# ioniq-v2.net
KiCad netlist of a schematic drawn in EAGLE
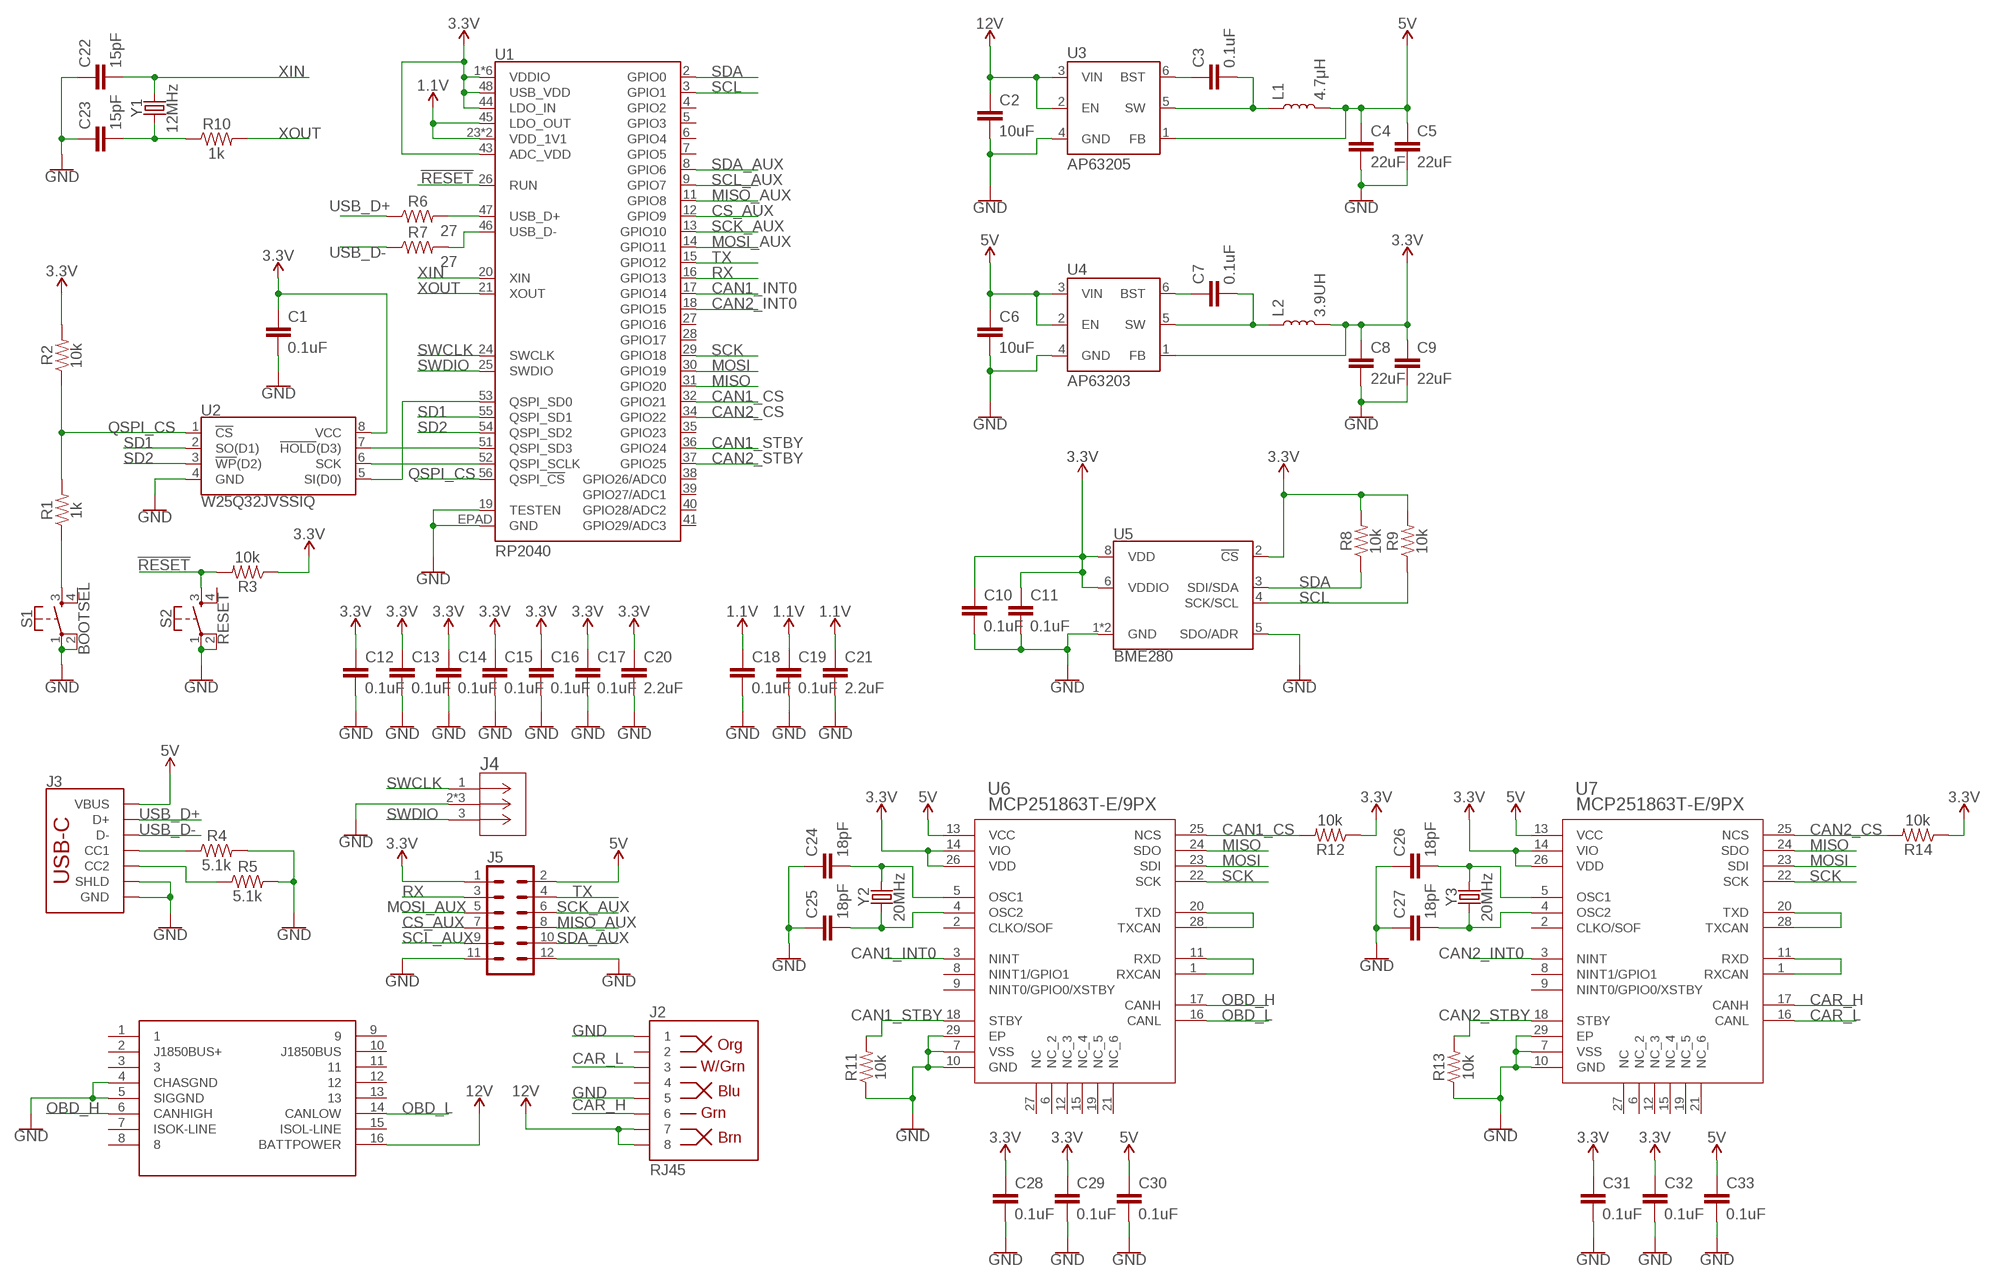
[diagram p0: schematic, sheet 1]

(export (version "E")
  (design (tool "Eeschema 10.0.6"))
  (components
    (comp (ref "C1")
      (value "0.1uF")
      (footprint "eagle-import:0603")
      (libsource (lib "eagle-import") (part "0.1UF-0603-25V-10%-X7R-WE"))
    )
    (comp (ref "C2")
      (value "10uF")
      (footprint "eagle-import:0805")
      (libsource (lib "eagle-import") (part "10UF-0805-25V-10%"))
    )
    (comp (ref "C3")
      (value "0.1uF")
      (footprint "eagle-import:0603")
      (libsource (lib "eagle-import") (part "0.1UF-0603-25V-5%"))
    )
    (comp (ref "C4")
      (value "22uF")
      (footprint "eagle-import:0603")
      (libsource (lib "eagle-import") (part "22UF-0603-6.3V-20%"))
    )
    (comp (ref "C5")
      (value "22uF")
      (footprint "eagle-import:0603")
      (libsource (lib "eagle-import") (part "22UF-0603-6.3V-20%"))
    )
    (comp (ref "C6")
      (value "10uF")
      (footprint "eagle-import:0805")
      (libsource (lib "eagle-import") (part "10UF-0805-25V-10%"))
    )
    (comp (ref "C7")
      (value "0.1uF")
      (footprint "eagle-import:0603")
      (libsource (lib "eagle-import") (part "0.1UF-0603-25V-5%"))
    )
    (comp (ref "C8")
      (value "22uF")
      (footprint "eagle-import:0603")
      (libsource (lib "eagle-import") (part "22UF-0603-6.3V-20%"))
    )
    (comp (ref "C9")
      (value "22uF")
      (footprint "eagle-import:0603")
      (libsource (lib "eagle-import") (part "22UF-0603-6.3V-20%"))
    )
    (comp (ref "C10")
      (value "0.1uF")
      (footprint "eagle-import:0603")
      (libsource (lib "eagle-import") (part "0.1UF-0603-25V-10%-X7R-WE"))
    )
    (comp (ref "C11")
      (value "0.1uF")
      (footprint "eagle-import:0603")
      (libsource (lib "eagle-import") (part "0.1UF-0603-25V-10%-X7R-WE"))
    )
    (comp (ref "C12")
      (value "0.1uF")
      (footprint "eagle-import:0603")
      (libsource (lib "eagle-import") (part "0.1UF-0603-25V-10%-X7R-WE"))
    )
    (comp (ref "C13")
      (value "0.1uF")
      (footprint "eagle-import:0603")
      (libsource (lib "eagle-import") (part "0.1UF-0603-25V-10%-X7R-WE"))
    )
    (comp (ref "C14")
      (value "0.1uF")
      (footprint "eagle-import:0603")
      (libsource (lib "eagle-import") (part "0.1UF-0603-25V-10%-X7R-WE"))
    )
    (comp (ref "C15")
      (value "0.1uF")
      (footprint "eagle-import:0603")
      (libsource (lib "eagle-import") (part "0.1UF-0603-25V-10%-X7R-WE"))
    )
    (comp (ref "C16")
      (value "0.1uF")
      (footprint "eagle-import:0603")
      (libsource (lib "eagle-import") (part "0.1UF-0603-25V-10%-X7R-WE"))
    )
    (comp (ref "C17")
      (value "0.1uF")
      (footprint "eagle-import:0603")
      (libsource (lib "eagle-import") (part "0.1UF-0603-25V-10%-X7R-WE"))
    )
    (comp (ref "C18")
      (value "0.1uF")
      (footprint "eagle-import:0603")
      (libsource (lib "eagle-import") (part "0.1UF-0603-25V-10%-X7R-WE"))
    )
    (comp (ref "C19")
      (value "0.1uF")
      (footprint "eagle-import:0603")
      (libsource (lib "eagle-import") (part "0.1UF-0603-25V-10%-X7R-WE"))
    )
    (comp (ref "C20")
      (value "2.2uF")
      (footprint "eagle-import:0603")
      (libsource (lib "eagle-import") (part "2.2UF-0603-10V-20%"))
    )
    (comp (ref "C21")
      (value "2.2uF")
      (footprint "eagle-import:0603")
      (libsource (lib "eagle-import") (part "2.2UF-0603-10V-20%"))
    )
    (comp (ref "C22")
      (value "15pF")
      (footprint "eagle-import:0603")
      (libsource (lib "eagle-import") (part "15PF-0603-50V-5%"))
    )
    (comp (ref "C23")
      (value "15pF")
      (footprint "eagle-import:0603")
      (libsource (lib "eagle-import") (part "15PF-0603-50V-5%"))
    )
    (comp (ref "C24")
      (value "18pF")
      (footprint "eagle-import:0603")
      (libsource (lib "eagle-import") (part "18PF-0603-50V-5%"))
    )
    (comp (ref "C25")
      (value "18pF")
      (footprint "eagle-import:0603")
      (libsource (lib "eagle-import") (part "18PF-0603-50V-5%"))
    )
    (comp (ref "C26")
      (value "18pF")
      (footprint "eagle-import:0603")
      (libsource (lib "eagle-import") (part "18PF-0603-50V-5%"))
    )
    (comp (ref "C27")
      (value "18pF")
      (footprint "eagle-import:0603")
      (libsource (lib "eagle-import") (part "18PF-0603-50V-5%"))
    )
    (comp (ref "C28")
      (value "0.1uF")
      (footprint "eagle-import:0603")
      (libsource (lib "eagle-import") (part "0.1UF-0603-25V-10%-X7R-WE"))
    )
    (comp (ref "C29")
      (value "0.1uF")
      (footprint "eagle-import:0603")
      (libsource (lib "eagle-import") (part "0.1UF-0603-25V-10%-X7R-WE"))
    )
    (comp (ref "C30")
      (value "0.1uF")
      (footprint "eagle-import:0603")
      (libsource (lib "eagle-import") (part "0.1UF-0603-25V-10%-X7R-WE"))
    )
    (comp (ref "C31")
      (value "0.1uF")
      (footprint "eagle-import:0603")
      (libsource (lib "eagle-import") (part "0.1UF-0603-25V-10%-X7R-WE"))
    )
    (comp (ref "C32")
      (value "0.1uF")
      (footprint "eagle-import:0603")
      (libsource (lib "eagle-import") (part "0.1UF-0603-25V-10%-X7R-WE"))
    )
    (comp (ref "C33")
      (value "0.1uF")
      (footprint "eagle-import:0603")
      (libsource (lib "eagle-import") (part "0.1UF-0603-25V-10%-X7R-WE"))
    )
    (comp (ref "J1")
      (value "OBDII")
      (footprint "eagle-import:OBDII")
      (libsource (lib "eagle-import") (part "OBDII"))
    )
    (comp (ref "J2")
      (value "RJ45")
      (footprint "eagle-import:RJ45-8")
      (libsource (lib "eagle-import") (part "RJ45-8"))
    )
    (comp (ref "J3")
      (value "USB_C_2-LAYER_PADS")
      (footprint "eagle-import:USB-C-16P-2LAYER-PADS")
      (libsource (lib "eagle-import") (part "USB_C_2-LAYER_PADS"))
    )
    (comp (ref "J4")
      (value "BM03B-SRSS-TB(LF)(SN)")
      (footprint "eagle-import:CONN_BM03B-SRSS-TB(LF)(SN)_JST")
      (fields (field (name "COPYRIGHT") "Copyright (C) 2024 Ultra Librarian. All rights reserved."))
      (libsource (lib "eagle-import") (part "BM03B-SRSS-TB(LF)(SN)"))
    )
    (comp (ref "J5")
      (value "2X6 FEMALE")
      (footprint "eagle-import:2X6")
      (libsource (lib "eagle-import") (part "CONN_06X2PTH_FEMALE"))
    )
    (comp (ref "L1")
      (value "4.7μH")
      (footprint "eagle-import:INDUCTOR_4X4MM")
      (libsource (lib "eagle-import") (part "4.7μH_SHIELDED_INDUCTORNPIS_LS"))
    )
    (comp (ref "L2")
      (value "3.9UH")
      (footprint "eagle-import:INDUCTOR_3.9UH")
      (libsource (lib "eagle-import") (part "3.9UH"))
    )
    (comp (ref "R1")
      (value "1k")
      (footprint "eagle-import:0603")
      (libsource (lib "eagle-import") (part "1KOHM-0603-1/10W-1%"))
    )
    (comp (ref "R2")
      (value "10k")
      (footprint "eagle-import:0603")
      (libsource (lib "eagle-import") (part "10KOHM-0603-1/10W-1%"))
    )
    (comp (ref "R3")
      (value "10k")
      (footprint "eagle-import:0603")
      (libsource (lib "eagle-import") (part "10KOHM-0603-1/10W-1%"))
    )
    (comp (ref "R4")
      (value "5.1k")
      (footprint "eagle-import:0603")
      (libsource (lib "eagle-import") (part "5.1KOHM5.1KOHM-0603-1/10W-1%"))
    )
    (comp (ref "R5")
      (value "5.1k")
      (footprint "eagle-import:0603")
      (libsource (lib "eagle-import") (part "5.1KOHM5.1KOHM-0603-1/10W-1%"))
    )
    (comp (ref "R6")
      (value "27")
      (footprint "eagle-import:0603")
      (libsource (lib "eagle-import") (part "27OHM-0603-1/10W-1%"))
    )
    (comp (ref "R7")
      (value "27")
      (footprint "eagle-import:0603")
      (libsource (lib "eagle-import") (part "27OHM-0603-1/10W-1%"))
    )
    (comp (ref "R8")
      (value "10k")
      (footprint "eagle-import:0603")
      (libsource (lib "eagle-import") (part "10KOHM-0603-1/10W-1%"))
    )
    (comp (ref "R9")
      (value "10k")
      (footprint "eagle-import:0603")
      (libsource (lib "eagle-import") (part "10KOHM-0603-1/10W-1%"))
    )
    (comp (ref "R10")
      (value "1k")
      (footprint "eagle-import:0603")
      (libsource (lib "eagle-import") (part "1KOHM-0603-1/10W-1%"))
    )
    (comp (ref "R11")
      (value "10k")
      (footprint "eagle-import:0603")
      (libsource (lib "eagle-import") (part "10KOHM-0603-1/10W-1%"))
    )
    (comp (ref "R12")
      (value "10k")
      (footprint "eagle-import:0603")
      (libsource (lib "eagle-import") (part "10KOHM-0603-1/10W-1%"))
    )
    (comp (ref "R13")
      (value "10k")
      (footprint "eagle-import:0603")
      (libsource (lib "eagle-import") (part "10KOHM-0603-1/10W-1%"))
    )
    (comp (ref "R14")
      (value "10k")
      (footprint "eagle-import:0603")
      (libsource (lib "eagle-import") (part "10KOHM-0603-1/10W-1%"))
    )
    (comp (ref "S1")
      (value "BOOTSEL")
      (footprint "eagle-import:TACTILE_SWITCH_SMD_4.6X2.8MM")
      (libsource (lib "eagle-import") (part "MOMENTARY-SWITCH-SPST-2-SMD-4.6X2.8MM"))
    )
    (comp (ref "S2")
      (value "RESET")
      (footprint "eagle-import:TACTILE_SWITCH_SMD_4.6X2.8MM")
      (libsource (lib "eagle-import") (part "MOMENTARY-SWITCH-SPST-2-SMD-4.6X2.8MM"))
    )
    (comp (ref "U1")
      (value "RP2040")
      (footprint "eagle-import:QFN-56")
      (libsource (lib "eagle-import") (part "RP2040"))
    )
    (comp (ref "U2")
      (value "W25Q32JVSSIQ")
      (footprint "eagle-import:SOIC-8")
      (libsource (lib "eagle-import") (part "W25Q32FVSS"))
    )
    (comp (ref "U3")
      (value "AP63205")
      (footprint "eagle-import:SOT23-6")
      (libsource (lib "eagle-import") (part "AP63203"))
    )
    (comp (ref "U4")
      (value "AP63203")
      (footprint "eagle-import:SOT23-6")
      (libsource (lib "eagle-import") (part "AP63203"))
    )
    (comp (ref "U5")
      (value "BME280")
      (footprint "eagle-import:LGA-8-2.5X2.5")
      (libsource (lib "eagle-import") (part "BME280"))
    )
    (comp (ref "U6")
      (value "MCP251863T-E/9PX")
      (footprint "eagle-import:VQFN28_9PX_3P25X3P25EPAD_MCH")
      (fields (field (name "COPYRIGHT") "Copyright (C) 2024 Ultra Librarian. All rights reserved."))
      (libsource (lib "eagle-import") (part "MCP251863T-E/9PX"))
    )
    (comp (ref "U7")
      (value "MCP251863T-E/9PX")
      (footprint "eagle-import:VQFN28_9PX_3P25X3P25EPAD_MCH")
      (fields (field (name "COPYRIGHT") "Copyright (C) 2024 Ultra Librarian. All rights reserved."))
      (libsource (lib "eagle-import") (part "MCP251863T-E/9PX"))
    )
    (comp (ref "Y1")
      (value "12MHz")
      (footprint "eagle-import:CRYSTAL-SMD-3.2X2.5MM")
      (libsource (lib "eagle-import") (part "CRYSTALSMD-3.2X2.5"))
    )
    (comp (ref "Y2")
      (value "20MHz")
      (footprint "eagle-import:CRYSTAL-SMD-3.2X2.5MM")
      (libsource (lib "eagle-import") (part "CRYSTALSMD-3.2X2.5"))
    )
    (comp (ref "Y3")
      (value "20MHz")
      (footprint "eagle-import:CRYSTAL-SMD-3.2X2.5MM")
      (libsource (lib "eagle-import") (part "CRYSTALSMD-3.2X2.5"))
    )
  )
  (nets
    (net (code "1") (name "/CAN1_CS") (class "Default")
      (node (ref "R12") (pin "2") (pinfunction "2_2") (pintype "passive"))
      (node (ref "U1") (pin "32") (pinfunction "GPIO21_32") (pintype "bidirectional"))
      (node (ref "U6") (pin "25") (pinfunction "NCS_25") (pintype "input"))
    )
    (net (code "2") (name "/CAN1_INT0") (class "Default")
      (node (ref "U1") (pin "17") (pinfunction "GPIO14_17") (pintype "bidirectional"))
      (node (ref "U6") (pin "3") (pinfunction "NINT_3") (pintype "output"))
    )
    (net (code "3") (name "/CAN1_STBY") (class "Default")
      (node (ref "R11") (pin "2") (pinfunction "2_2") (pintype "passive"))
      (node (ref "U1") (pin "36") (pinfunction "GPIO24_36") (pintype "bidirectional"))
      (node (ref "U6") (pin "18") (pinfunction "STBY_18") (pintype "input"))
    )
    (net (code "4") (name "/CAN2_CS") (class "Default")
      (node (ref "R14") (pin "2") (pinfunction "2_2") (pintype "passive"))
      (node (ref "U1") (pin "34") (pinfunction "GPIO22_34") (pintype "bidirectional"))
      (node (ref "U7") (pin "25") (pinfunction "NCS_25") (pintype "input"))
    )
    (net (code "5") (name "/CAN2_INT0") (class "Default")
      (node (ref "U1") (pin "18") (pinfunction "GPIO15_18") (pintype "bidirectional"))
      (node (ref "U7") (pin "3") (pinfunction "NINT_3") (pintype "output"))
    )
    (net (code "6") (name "/CAN2_STBY") (class "Default")
      (node (ref "R13") (pin "2") (pinfunction "2_2") (pintype "passive"))
      (node (ref "U1") (pin "37") (pinfunction "GPIO25_37") (pintype "bidirectional"))
      (node (ref "U7") (pin "18") (pinfunction "STBY_18") (pintype "input"))
    )
    (net (code "7") (name "/CAR_H") (class "Default")
      (node (ref "J2") (pin "6") (pinfunction "6_6") (pintype "bidirectional"))
      (node (ref "U7") (pin "17") (pinfunction "CANH_17") (pintype "bidirectional"))
    )
    (net (code "8") (name "/CAR_L") (class "Default")
      (node (ref "J2") (pin "3") (pinfunction "3_3") (pintype "bidirectional"))
      (node (ref "U7") (pin "16") (pinfunction "CANL_16") (pintype "bidirectional"))
    )
    (net (code "9") (name "/CS_AUX") (class "Default")
      (node (ref "J5") (pin "7") (pinfunction "7_7") (pintype "passive"))
      (node (ref "U1") (pin "12") (pinfunction "GPIO9_12") (pintype "bidirectional"))
    )
    (net (code "10") (name "/MISO") (class "Default")
      (node (ref "U1") (pin "31") (pinfunction "GPIO20_31") (pintype "bidirectional"))
      (node (ref "U6") (pin "24") (pinfunction "SDO_24") (pintype "output"))
      (node (ref "U7") (pin "24") (pinfunction "SDO_24") (pintype "output"))
    )
    (net (code "11") (name "/MISO_AUX") (class "Default")
      (node (ref "J5") (pin "8") (pinfunction "8_8") (pintype "passive"))
      (node (ref "U1") (pin "11") (pinfunction "GPIO8_11") (pintype "bidirectional"))
    )
    (net (code "12") (name "/MOSI") (class "Default")
      (node (ref "U1") (pin "30") (pinfunction "GPIO19_30") (pintype "bidirectional"))
      (node (ref "U6") (pin "23") (pinfunction "SDI_23") (pintype "input"))
      (node (ref "U7") (pin "23") (pinfunction "SDI_23") (pintype "input"))
    )
    (net (code "13") (name "/MOSI_AUX") (class "Default")
      (node (ref "J5") (pin "5") (pinfunction "5_5") (pintype "passive"))
      (node (ref "U1") (pin "14") (pinfunction "GPIO11_14") (pintype "bidirectional"))
    )
    (net (code "14") (name "/OBD_H") (class "Default")
      (node (ref "J1") (pin "6") (pinfunction "CANHIGH_6") (pintype "bidirectional"))
      (node (ref "U6") (pin "17") (pinfunction "CANH_17") (pintype "bidirectional"))
    )
    (net (code "15") (name "/OBD_L") (class "Default")
      (node (ref "J1") (pin "14") (pinfunction "CANLOW_14") (pintype "bidirectional"))
      (node (ref "U6") (pin "16") (pinfunction "CANL_16") (pintype "bidirectional"))
    )
    (net (code "16") (name "/QSPI_CS") (class "Default")
      (node (ref "R1") (pin "2") (pinfunction "2_2") (pintype "passive"))
      (node (ref "R2") (pin "1") (pinfunction "1_1") (pintype "passive"))
      (node (ref "U1") (pin "56") (pinfunction "QSPI_~{CS}_56") (pintype "bidirectional"))
      (node (ref "U2") (pin "1") (pinfunction "~{CS}_1") (pintype "bidirectional"))
    )
    (net (code "17") (name "/RX") (class "Default")
      (node (ref "J5") (pin "3") (pinfunction "3_3") (pintype "passive"))
      (node (ref "U1") (pin "16") (pinfunction "GPIO13_16") (pintype "bidirectional"))
    )
    (net (code "18") (name "/SCK") (class "Default")
      (node (ref "U1") (pin "29") (pinfunction "GPIO18_29") (pintype "bidirectional"))
      (node (ref "U6") (pin "22") (pinfunction "SCK_22") (pintype "input"))
      (node (ref "U7") (pin "22") (pinfunction "SCK_22") (pintype "input"))
    )
    (net (code "19") (name "/SCK_AUX") (class "Default")
      (node (ref "J5") (pin "6") (pinfunction "6_6") (pintype "passive"))
      (node (ref "U1") (pin "13") (pinfunction "GPIO10_13") (pintype "bidirectional"))
    )
    (net (code "20") (name "/SCL") (class "Default")
      (node (ref "R9") (pin "1") (pinfunction "1_1") (pintype "passive"))
      (node (ref "U1") (pin "3") (pinfunction "GPIO1_3") (pintype "bidirectional"))
      (node (ref "U5") (pin "4") (pinfunction "SCK/SCL_4") (pintype "bidirectional"))
    )
    (net (code "21") (name "/SCL_AUX") (class "Default")
      (node (ref "J5") (pin "9") (pinfunction "9_9") (pintype "passive"))
      (node (ref "U1") (pin "9") (pinfunction "GPIO7_9") (pintype "bidirectional"))
    )
    (net (code "22") (name "/SD1") (class "Default")
      (node (ref "U1") (pin "55") (pinfunction "QSPI_SD1_55") (pintype "bidirectional"))
      (node (ref "U2") (pin "2") (pinfunction "SO(D1)_2") (pintype "bidirectional"))
    )
    (net (code "23") (name "/SD2") (class "Default")
      (node (ref "U1") (pin "54") (pinfunction "QSPI_SD2_54") (pintype "bidirectional"))
      (node (ref "U2") (pin "3") (pinfunction "~{WP}(D2)_3") (pintype "bidirectional"))
    )
    (net (code "24") (name "/SDA") (class "Default")
      (node (ref "R8") (pin "1") (pinfunction "1_1") (pintype "passive"))
      (node (ref "U1") (pin "2") (pinfunction "GPIO0_2") (pintype "bidirectional"))
      (node (ref "U5") (pin "3") (pinfunction "SDI/SDA_3") (pintype "bidirectional"))
    )
    (net (code "25") (name "/SDA_AUX") (class "Default")
      (node (ref "J5") (pin "10") (pinfunction "10_10") (pintype "passive"))
      (node (ref "U1") (pin "8") (pinfunction "GPIO6_8") (pintype "bidirectional"))
    )
    (net (code "26") (name "/SWCLK") (class "Default")
      (node (ref "J4") (pin "1") (pinfunction "1_1") (pintype "passive"))
      (node (ref "U1") (pin "24") (pinfunction "SWCLK_24") (pintype "bidirectional"))
    )
    (net (code "27") (name "/SWDIO") (class "Default")
      (node (ref "J4") (pin "3") (pinfunction "3_3") (pintype "passive"))
      (node (ref "U1") (pin "25") (pinfunction "SWDIO_25") (pintype "bidirectional"))
    )
    (net (code "28") (name "/TX") (class "Default")
      (node (ref "J5") (pin "4") (pinfunction "4_4") (pintype "passive"))
      (node (ref "U1") (pin "15") (pinfunction "GPIO12_15") (pintype "bidirectional"))
    )
    (net (code "29") (name "/USB_D+") (class "Default")
      (node (ref "J3") (pin "A6") (pinfunction "D+_A6") (pintype "bidirectional"))
      (node (ref "J3") (pin "B6") (pinfunction "D+_B6") (pintype "bidirectional"))
      (node (ref "R6") (pin "1") (pinfunction "1_1") (pintype "passive"))
    )
    (net (code "30") (name "/USB_D-") (class "Default")
      (node (ref "J3") (pin "A7") (pinfunction "D-_A7") (pintype "bidirectional"))
      (node (ref "J3") (pin "B7") (pinfunction "D-_B7") (pintype "bidirectional"))
      (node (ref "R7") (pin "1") (pinfunction "1_1") (pintype "passive"))
    )
    (net (code "31") (name "/XIN") (class "Default")
      (node (ref "C22") (pin "2") (pinfunction "2_2") (pintype "passive"))
      (node (ref "U1") (pin "20") (pinfunction "XIN_20") (pintype "bidirectional"))
      (node (ref "Y1") (pin "3") (pinfunction "2_3") (pintype "passive"))
    )
    (net (code "32") (name "/XOUT") (class "Default")
      (node (ref "R10") (pin "2") (pinfunction "2_2") (pintype "passive"))
      (node (ref "U1") (pin "21") (pinfunction "XOUT_21") (pintype "bidirectional"))
    )
    (net (code "33") (name "/~{RESET}") (class "Default")
      (node (ref "R3") (pin "2") (pinfunction "2_2") (pintype "passive"))
      (node (ref "S2") (pin "3") (pinfunction "3_3") (pintype "passive"))
      (node (ref "U1") (pin "26") (pinfunction "RUN_26") (pintype "bidirectional"))
    )
    (net (code "34") (name "1.1V") (class "Default")
      (node (ref "C18") (pin "1") (pinfunction "1_1") (pintype "passive"))
      (node (ref "C19") (pin "1") (pinfunction "1_1") (pintype "passive"))
      (node (ref "C21") (pin "1") (pinfunction "1_1") (pintype "passive"))
      (node (ref "U1") (pin "23") (pinfunction "VDD_1V1_23") (pintype "bidirectional"))
      (node (ref "U1") (pin "45") (pinfunction "LDO_OUT_45") (pintype "bidirectional"))
      (node (ref "U1") (pin "50") (pinfunction "VDD_1V1_50") (pintype "bidirectional"))
    )
    (net (code "35") (name "3.3V") (class "Default")
      (node (ref "C1") (pin "1") (pinfunction "1_1") (pintype "passive"))
      (node (ref "C10") (pin "1") (pinfunction "1_1") (pintype "passive"))
      (node (ref "C11") (pin "1") (pinfunction "1_1") (pintype "passive"))
      (node (ref "C12") (pin "1") (pinfunction "1_1") (pintype "passive"))
      (node (ref "C13") (pin "1") (pinfunction "1_1") (pintype "passive"))
      (node (ref "C14") (pin "1") (pinfunction "1_1") (pintype "passive"))
      (node (ref "C15") (pin "1") (pinfunction "1_1") (pintype "passive"))
      (node (ref "C16") (pin "1") (pinfunction "1_1") (pintype "passive"))
      (node (ref "C17") (pin "1") (pinfunction "1_1") (pintype "passive"))
      (node (ref "C20") (pin "1") (pinfunction "1_1") (pintype "passive"))
      (node (ref "C28") (pin "1") (pinfunction "1_1") (pintype "passive"))
      (node (ref "C29") (pin "1") (pinfunction "1_1") (pintype "passive"))
      (node (ref "C31") (pin "1") (pinfunction "1_1") (pintype "passive"))
      (node (ref "C32") (pin "1") (pinfunction "1_1") (pintype "passive"))
      (node (ref "C8") (pin "1") (pinfunction "1_1") (pintype "passive"))
      (node (ref "C9") (pin "1") (pinfunction "1_1") (pintype "passive"))
      (node (ref "J5") (pin "1") (pinfunction "1_1") (pintype "passive"))
      (node (ref "L2") (pin "P$2") (pinfunction "2_P$2") (pintype "passive"))
      (node (ref "R12") (pin "1") (pinfunction "1_1") (pintype "passive"))
      (node (ref "R14") (pin "1") (pinfunction "1_1") (pintype "passive"))
      (node (ref "R2") (pin "2") (pinfunction "2_2") (pintype "passive"))
      (node (ref "R3") (pin "1") (pinfunction "1_1") (pintype "passive"))
      (node (ref "R8") (pin "2") (pinfunction "2_2") (pintype "passive"))
      (node (ref "R9") (pin "2") (pinfunction "2_2") (pintype "passive"))
      (node (ref "U1") (pin "1") (pinfunction "VDDIO_1") (pintype "bidirectional"))
      (node (ref "U1") (pin "10") (pinfunction "VDDIO_10") (pintype "bidirectional"))
      (node (ref "U1") (pin "22") (pinfunction "VDDIO_22") (pintype "bidirectional"))
      (node (ref "U1") (pin "33") (pinfunction "VDDIO_33") (pintype "bidirectional"))
      (node (ref "U1") (pin "42") (pinfunction "VDDIO_42") (pintype "bidirectional"))
      (node (ref "U1") (pin "43") (pinfunction "ADC_VDD_43") (pintype "bidirectional"))
      (node (ref "U1") (pin "44") (pinfunction "LDO_IN_44") (pintype "bidirectional"))
      (node (ref "U1") (pin "48") (pinfunction "USB_VDD_48") (pintype "bidirectional"))
      (node (ref "U1") (pin "49") (pinfunction "VDDIO_49") (pintype "bidirectional"))
      (node (ref "U2") (pin "8") (pinfunction "VCC_8") (pintype "bidirectional"))
      (node (ref "U4") (pin "1") (pinfunction "FB_1") (pintype "bidirectional"))
      (node (ref "U5") (pin "2") (pinfunction "~{CS}_2") (pintype "bidirectional"))
      (node (ref "U5") (pin "6") (pinfunction "VDDIO_6") (pintype "bidirectional"))
      (node (ref "U5") (pin "8") (pinfunction "VDD_8") (pintype "bidirectional"))
      (node (ref "U6") (pin "14") (pinfunction "VIO_14") (pintype "power_in"))
      (node (ref "U6") (pin "26") (pinfunction "VDD_26") (pintype "power_in"))
      (node (ref "U7") (pin "14") (pinfunction "VIO_14") (pintype "power_in"))
      (node (ref "U7") (pin "26") (pinfunction "VDD_26") (pintype "power_in"))
    )
    (net (code "36") (name "5V") (class "Default")
      (node (ref "C30") (pin "1") (pinfunction "1_1") (pintype "passive"))
      (node (ref "C33") (pin "1") (pinfunction "1_1") (pintype "passive"))
      (node (ref "C4") (pin "1") (pinfunction "1_1") (pintype "passive"))
      (node (ref "C5") (pin "1") (pinfunction "1_1") (pintype "passive"))
      (node (ref "C6") (pin "1") (pinfunction "1_1") (pintype "passive"))
      (node (ref "J3") (pin "VBUS1") (pinfunction "VBUS_VBUS1") (pintype "bidirectional"))
      (node (ref "J3") (pin "VBUS2") (pinfunction "VBUS_VBUS2") (pintype "bidirectional"))
      (node (ref "J5") (pin "2") (pinfunction "2_2") (pintype "passive"))
      (node (ref "L1") (pin "P$2") (pinfunction "2_P$2") (pintype "passive"))
      (node (ref "U3") (pin "1") (pinfunction "FB_1") (pintype "bidirectional"))
      (node (ref "U4") (pin "2") (pinfunction "EN_2") (pintype "bidirectional"))
      (node (ref "U4") (pin "3") (pinfunction "VIN_3") (pintype "bidirectional"))
      (node (ref "U6") (pin "13") (pinfunction "VCC_13") (pintype "power_in"))
      (node (ref "U7") (pin "13") (pinfunction "VCC_13") (pintype "power_in"))
    )
    (net (code "37") (name "12V") (class "Default")
      (node (ref "C2") (pin "1") (pinfunction "1_1") (pintype "passive"))
      (node (ref "J1") (pin "16") (pinfunction "BATTPOWER_16") (pintype "bidirectional"))
      (node (ref "J2") (pin "7") (pinfunction "7_7") (pintype "bidirectional"))
      (node (ref "J2") (pin "8") (pinfunction "8_8") (pintype "bidirectional"))
      (node (ref "U3") (pin "2") (pinfunction "EN_2") (pintype "bidirectional"))
      (node (ref "U3") (pin "3") (pinfunction "VIN_3") (pintype "bidirectional"))
    )
    (net (code "38") (name "GND") (class "Default")
      (node (ref "C1") (pin "2") (pinfunction "2_2") (pintype "passive"))
      (node (ref "C10") (pin "2") (pinfunction "2_2") (pintype "passive"))
      (node (ref "C11") (pin "2") (pinfunction "2_2") (pintype "passive"))
      (node (ref "C12") (pin "2") (pinfunction "2_2") (pintype "passive"))
      (node (ref "C13") (pin "2") (pinfunction "2_2") (pintype "passive"))
      (node (ref "C14") (pin "2") (pinfunction "2_2") (pintype "passive"))
      (node (ref "C15") (pin "2") (pinfunction "2_2") (pintype "passive"))
      (node (ref "C16") (pin "2") (pinfunction "2_2") (pintype "passive"))
      (node (ref "C17") (pin "2") (pinfunction "2_2") (pintype "passive"))
      (node (ref "C18") (pin "2") (pinfunction "2_2") (pintype "passive"))
      (node (ref "C19") (pin "2") (pinfunction "2_2") (pintype "passive"))
      (node (ref "C2") (pin "2") (pinfunction "2_2") (pintype "passive"))
      (node (ref "C20") (pin "2") (pinfunction "2_2") (pintype "passive"))
      (node (ref "C21") (pin "2") (pinfunction "2_2") (pintype "passive"))
      (node (ref "C22") (pin "1") (pinfunction "1_1") (pintype "passive"))
      (node (ref "C23") (pin "1") (pinfunction "1_1") (pintype "passive"))
      (node (ref "C24") (pin "1") (pinfunction "1_1") (pintype "passive"))
      (node (ref "C25") (pin "1") (pinfunction "1_1") (pintype "passive"))
      (node (ref "C26") (pin "1") (pinfunction "1_1") (pintype "passive"))
      (node (ref "C27") (pin "1") (pinfunction "1_1") (pintype "passive"))
      (node (ref "C28") (pin "2") (pinfunction "2_2") (pintype "passive"))
      (node (ref "C29") (pin "2") (pinfunction "2_2") (pintype "passive"))
      (node (ref "C30") (pin "2") (pinfunction "2_2") (pintype "passive"))
      (node (ref "C31") (pin "2") (pinfunction "2_2") (pintype "passive"))
      (node (ref "C32") (pin "2") (pinfunction "2_2") (pintype "passive"))
      (node (ref "C33") (pin "2") (pinfunction "2_2") (pintype "passive"))
      (node (ref "C4") (pin "2") (pinfunction "2_2") (pintype "passive"))
      (node (ref "C5") (pin "2") (pinfunction "2_2") (pintype "passive"))
      (node (ref "C6") (pin "2") (pinfunction "2_2") (pintype "passive"))
      (node (ref "C8") (pin "2") (pinfunction "2_2") (pintype "passive"))
      (node (ref "C9") (pin "2") (pinfunction "2_2") (pintype "passive"))
      (node (ref "J1") (pin "4") (pinfunction "CHASGND_4") (pintype "bidirectional"))
      (node (ref "J1") (pin "5") (pinfunction "SIGGND_5") (pintype "bidirectional"))
      (node (ref "J2") (pin "1") (pinfunction "1_1") (pintype "bidirectional"))
      (node (ref "J2") (pin "5") (pinfunction "5_5") (pintype "bidirectional"))
      (node (ref "J3") (pin "GND") (pinfunction "GND_GND") (pintype "bidirectional"))
      (node (ref "J3") (pin "GND2") (pinfunction "GND_GND2") (pintype "bidirectional"))
      (node (ref "J3") (pin "SHLD1") (pinfunction "SHLD_SHLD1") (pintype "bidirectional"))
      (node (ref "J3") (pin "SHLD2") (pinfunction "SHLD_SHLD2") (pintype "bidirectional"))
      (node (ref "J3") (pin "SHLD3") (pinfunction "SHLD_SHLD3") (pintype "bidirectional"))
      (node (ref "J3") (pin "SHLD4") (pinfunction "SHLD_SHLD4") (pintype "bidirectional"))
      (node (ref "J4") (pin "2") (pinfunction "2_2") (pintype "passive"))
      (node (ref "J4") (pin "4") (pinfunction "2_4") (pintype "passive"))
      (node (ref "J4") (pin "5") (pinfunction "2_5") (pintype "passive"))
      (node (ref "J5") (pin "11") (pinfunction "11_11") (pintype "passive"))
      (node (ref "J5") (pin "12") (pinfunction "12_12") (pintype "passive"))
      (node (ref "R11") (pin "1") (pinfunction "1_1") (pintype "passive"))
      (node (ref "R13") (pin "1") (pinfunction "1_1") (pintype "passive"))
      (node (ref "R4") (pin "2") (pinfunction "2_2") (pintype "passive"))
      (node (ref "R5") (pin "2") (pinfunction "2_2") (pintype "passive"))
      (node (ref "S1") (pin "1") (pinfunction "1_1") (pintype "passive"))
      (node (ref "S1") (pin "2") (pinfunction "2_2") (pintype "passive"))
      (node (ref "S2") (pin "1") (pinfunction "1_1") (pintype "passive"))
      (node (ref "S2") (pin "2") (pinfunction "2_2") (pintype "passive"))
      (node (ref "U1") (pin "19") (pinfunction "TESTEN_19") (pintype "bidirectional"))
      (node (ref "U1") (pin "EPAD") (pinfunction "GND_EPAD") (pintype "bidirectional"))
      (node (ref "U2") (pin "4") (pinfunction "GND_4") (pintype "bidirectional"))
      (node (ref "U3") (pin "4") (pinfunction "GND_4") (pintype "bidirectional"))
      (node (ref "U4") (pin "4") (pinfunction "GND_4") (pintype "bidirectional"))
      (node (ref "U5") (pin "1") (pinfunction "GND_1") (pintype "bidirectional"))
      (node (ref "U5") (pin "5") (pinfunction "SDO/ADR_5") (pintype "bidirectional"))
      (node (ref "U5") (pin "7") (pinfunction "GND_7") (pintype "bidirectional"))
      (node (ref "U6") (pin "10") (pinfunction "GND_10") (pintype "passive"))
      (node (ref "U6") (pin "29") (pinfunction "EP_29") (pintype "passive"))
      (node (ref "U6") (pin "7") (pinfunction "VSS_7") (pintype "passive"))
      (node (ref "U7") (pin "10") (pinfunction "GND_10") (pintype "passive"))
      (node (ref "U7") (pin "29") (pinfunction "EP_29") (pintype "passive"))
      (node (ref "U7") (pin "7") (pinfunction "VSS_7") (pintype "passive"))
    )
    (net (code "39") (name "Net-(C23-Pad2)") (class "Default")
      (node (ref "C23") (pin "2") (pinfunction "2_2") (pintype "passive"))
      (node (ref "R10") (pin "1") (pinfunction "1_1") (pintype "passive"))
      (node (ref "Y1") (pin "1") (pinfunction "1_1") (pintype "passive"))
    )
    (net (code "40") (name "Net-(J3-CC1)") (class "Default")
      (node (ref "J3") (pin "A5") (pinfunction "CC1_A5") (pintype "bidirectional"))
      (node (ref "R4") (pin "1") (pinfunction "1_1") (pintype "passive"))
    )
    (net (code "41") (name "Net-(J3-CC2)") (class "Default")
      (node (ref "J3") (pin "B5") (pinfunction "CC2_B5") (pintype "bidirectional"))
      (node (ref "R5") (pin "1") (pinfunction "1_1") (pintype "passive"))
    )
    (net (code "42") (name "Net-(L1-1)") (class "Default")
      (node (ref "C3") (pin "2") (pinfunction "2_2") (pintype "passive"))
      (node (ref "L1") (pin "P$1") (pinfunction "1_P$1") (pintype "passive"))
      (node (ref "U3") (pin "5") (pinfunction "SW_5") (pintype "bidirectional"))
    )
    (net (code "43") (name "Net-(L2-1)") (class "Default")
      (node (ref "C7") (pin "2") (pinfunction "2_2") (pintype "passive"))
      (node (ref "L2") (pin "P$1") (pinfunction "1_P$1") (pintype "passive"))
      (node (ref "U4") (pin "5") (pinfunction "SW_5") (pintype "bidirectional"))
    )
    (net (code "44") (name "Net-(R1-Pad1)") (class "Default")
      (node (ref "R1") (pin "1") (pinfunction "1_1") (pintype "passive"))
      (node (ref "S1") (pin "3") (pinfunction "3_3") (pintype "passive"))
    )
    (net (code "45") (name "Net-(U1-QSPI_SCLK)") (class "Default")
      (node (ref "U1") (pin "52") (pinfunction "QSPI_SCLK_52") (pintype "bidirectional"))
      (node (ref "U2") (pin "6") (pinfunction "SCK_6") (pintype "bidirectional"))
    )
    (net (code "46") (name "Net-(U1-QSPI_SD0)") (class "Default")
      (node (ref "U1") (pin "53") (pinfunction "QSPI_SD0_53") (pintype "bidirectional"))
      (node (ref "U2") (pin "5") (pinfunction "SI(D0)_5") (pintype "bidirectional"))
    )
    (net (code "47") (name "Net-(U1-QSPI_SD3)") (class "Default")
      (node (ref "U1") (pin "51") (pinfunction "QSPI_SD3_51") (pintype "bidirectional"))
      (node (ref "U2") (pin "7") (pinfunction "~{HOLD}(D3)_7") (pintype "bidirectional"))
    )
    (net (code "48") (name "Net-(U1-USB_D+)") (class "Default")
      (node (ref "R6") (pin "2") (pinfunction "2_2") (pintype "passive"))
      (node (ref "U1") (pin "47") (pinfunction "USB_D+_47") (pintype "bidirectional"))
    )
    (net (code "49") (name "Net-(U1-USB_D-)") (class "Default")
      (node (ref "R7") (pin "2") (pinfunction "2_2") (pintype "passive"))
      (node (ref "U1") (pin "46") (pinfunction "USB_D-_46") (pintype "bidirectional"))
    )
    (net (code "50") (name "Net-(U3-BST)") (class "Default")
      (node (ref "C3") (pin "1") (pinfunction "1_1") (pintype "passive"))
      (node (ref "U3") (pin "6") (pinfunction "BST_6") (pintype "bidirectional"))
    )
    (net (code "51") (name "Net-(U4-BST)") (class "Default")
      (node (ref "C7") (pin "1") (pinfunction "1_1") (pintype "passive"))
      (node (ref "U4") (pin "6") (pinfunction "BST_6") (pintype "bidirectional"))
    )
    (net (code "52") (name "Net-(U6-OSC1)") (class "Default")
      (node (ref "C24") (pin "2") (pinfunction "2_2") (pintype "passive"))
      (node (ref "U6") (pin "5") (pinfunction "OSC1_5") (pintype "input"))
      (node (ref "Y2") (pin "3") (pinfunction "2_3") (pintype "passive"))
    )
    (net (code "53") (name "Net-(U6-OSC2)") (class "Default")
      (node (ref "C25") (pin "2") (pinfunction "2_2") (pintype "passive"))
      (node (ref "U6") (pin "4") (pinfunction "OSC2_4") (pintype "output"))
      (node (ref "Y2") (pin "1") (pinfunction "1_1") (pintype "passive"))
    )
    (net (code "54") (name "Net-(U6-RXCAN)") (class "Default")
      (node (ref "U6") (pin "1") (pinfunction "RXCAN_1") (pintype "input"))
      (node (ref "U6") (pin "11") (pinfunction "RXD_11") (pintype "output"))
    )
    (net (code "55") (name "Net-(U6-TXCAN)") (class "Default")
      (node (ref "U6") (pin "20") (pinfunction "TXD_20") (pintype "input"))
      (node (ref "U6") (pin "28") (pinfunction "TXCAN_28") (pintype "output"))
    )
    (net (code "56") (name "Net-(U7-OSC1)") (class "Default")
      (node (ref "C26") (pin "2") (pinfunction "2_2") (pintype "passive"))
      (node (ref "U7") (pin "5") (pinfunction "OSC1_5") (pintype "input"))
      (node (ref "Y3") (pin "3") (pinfunction "2_3") (pintype "passive"))
    )
    (net (code "57") (name "Net-(U7-OSC2)") (class "Default")
      (node (ref "C27") (pin "2") (pinfunction "2_2") (pintype "passive"))
      (node (ref "U7") (pin "4") (pinfunction "OSC2_4") (pintype "output"))
      (node (ref "Y3") (pin "1") (pinfunction "1_1") (pintype "passive"))
    )
    (net (code "58") (name "Net-(U7-RXCAN)") (class "Default")
      (node (ref "U7") (pin "1") (pinfunction "RXCAN_1") (pintype "input"))
      (node (ref "U7") (pin "11") (pinfunction "RXD_11") (pintype "output"))
    )
    (net (code "59") (name "Net-(U7-TXCAN)") (class "Default")
      (node (ref "U7") (pin "20") (pinfunction "TXD_20") (pintype "input"))
      (node (ref "U7") (pin "28") (pinfunction "TXCAN_28") (pintype "output"))
    )
    (net (code "60") (name "unconnected-(J1-ISOK-LINE-Pad7)") (class "Default")
      (node (ref "J1") (pin "7") (pinfunction "ISOK-LINE_7") (pintype "bidirectional"))
    )
    (net (code "61") (name "unconnected-(J1-ISOL-LINE-Pad15)") (class "Default")
      (node (ref "J1") (pin "15") (pinfunction "ISOL-LINE_15") (pintype "bidirectional"))
    )
    (net (code "62") (name "unconnected-(J1-J1850BUS+-Pad2)") (class "Default")
      (node (ref "J1") (pin "2") (pinfunction "J1850BUS+_2") (pintype "bidirectional"))
    )
    (net (code "63") (name "unconnected-(J1-J1850BUS-Pad10)") (class "Default")
      (node (ref "J1") (pin "10") (pinfunction "J1850BUS_10") (pintype "bidirectional"))
    )
    (net (code "64") (name "unconnected-(J1-Pad1)") (class "Default")
      (node (ref "J1") (pin "1") (pinfunction "1_1") (pintype "bidirectional"))
    )
    (net (code "65") (name "unconnected-(J1-Pad3)") (class "Default")
      (node (ref "J1") (pin "3") (pinfunction "3_3") (pintype "bidirectional"))
    )
    (net (code "66") (name "unconnected-(J1-Pad8)") (class "Default")
      (node (ref "J1") (pin "8") (pinfunction "8_8") (pintype "bidirectional"))
    )
    (net (code "67") (name "unconnected-(J1-Pad9)") (class "Default")
      (node (ref "J1") (pin "9") (pinfunction "9_9") (pintype "bidirectional"))
    )
    (net (code "68") (name "unconnected-(J1-Pad11)") (class "Default")
      (node (ref "J1") (pin "11") (pinfunction "11_11") (pintype "bidirectional"))
    )
    (net (code "69") (name "unconnected-(J1-Pad12)") (class "Default")
      (node (ref "J1") (pin "12") (pinfunction "12_12") (pintype "bidirectional"))
    )
    (net (code "70") (name "unconnected-(J1-Pad13)") (class "Default")
      (node (ref "J1") (pin "13") (pinfunction "13_13") (pintype "bidirectional"))
    )
    (net (code "71") (name "unconnected-(J2-Pad2)") (class "Default")
      (node (ref "J2") (pin "2") (pinfunction "2_2") (pintype "bidirectional"))
    )
    (net (code "72") (name "unconnected-(J2-Pad4)") (class "Default")
      (node (ref "J2") (pin "4") (pinfunction "4_4") (pintype "bidirectional"))
    )
    (net (code "73") (name "unconnected-(S1-Pad4)") (class "Default")
      (node (ref "S1") (pin "4") (pinfunction "4_4") (pintype "passive"))
    )
    (net (code "74") (name "unconnected-(S2-Pad4)") (class "Default")
      (node (ref "S2") (pin "4") (pinfunction "4_4") (pintype "passive"))
    )
    (net (code "75") (name "unconnected-(U1-GPIO2-Pad4)") (class "Default")
      (node (ref "U1") (pin "4") (pinfunction "GPIO2_4") (pintype "bidirectional"))
    )
    (net (code "76") (name "unconnected-(U1-GPIO3-Pad5)") (class "Default")
      (node (ref "U1") (pin "5") (pinfunction "GPIO3_5") (pintype "bidirectional"))
    )
    (net (code "77") (name "unconnected-(U1-GPIO4-Pad6)") (class "Default")
      (node (ref "U1") (pin "6") (pinfunction "GPIO4_6") (pintype "bidirectional"))
    )
    (net (code "78") (name "unconnected-(U1-GPIO5-Pad7)") (class "Default")
      (node (ref "U1") (pin "7") (pinfunction "GPIO5_7") (pintype "bidirectional"))
    )
    (net (code "79") (name "unconnected-(U1-GPIO16-Pad27)") (class "Default")
      (node (ref "U1") (pin "27") (pinfunction "GPIO16_27") (pintype "bidirectional"))
    )
    (net (code "80") (name "unconnected-(U1-GPIO17-Pad28)") (class "Default")
      (node (ref "U1") (pin "28") (pinfunction "GPIO17_28") (pintype "bidirectional"))
    )
    (net (code "81") (name "unconnected-(U1-GPIO23-Pad35)") (class "Default")
      (node (ref "U1") (pin "35") (pinfunction "GPIO23_35") (pintype "bidirectional"))
    )
    (net (code "82") (name "unconnected-(U1-GPIO26{slash}ADC0-Pad38)") (class "Default")
      (node (ref "U1") (pin "38") (pinfunction "GPIO26/ADC0_38") (pintype "bidirectional"))
    )
    (net (code "83") (name "unconnected-(U1-GPIO27{slash}ADC1-Pad39)") (class "Default")
      (node (ref "U1") (pin "39") (pinfunction "GPIO27/ADC1_39") (pintype "bidirectional"))
    )
    (net (code "84") (name "unconnected-(U1-GPIO28{slash}ADC2-Pad40)") (class "Default")
      (node (ref "U1") (pin "40") (pinfunction "GPIO28/ADC2_40") (pintype "bidirectional"))
    )
    (net (code "85") (name "unconnected-(U1-GPIO29{slash}ADC3-Pad41)") (class "Default")
      (node (ref "U1") (pin "41") (pinfunction "GPIO29/ADC3_41") (pintype "bidirectional"))
    )
    (net (code "86") (name "unconnected-(U6-CLKO{slash}SOF-Pad2)") (class "Default")
      (node (ref "U6") (pin "2") (pinfunction "CLKO/SOF_2") (pintype "output"))
    )
    (net (code "87") (name "unconnected-(U6-NC-Pad27)") (class "Default")
      (node (ref "U6") (pin "27") (pinfunction "NC_27") (pintype "no_connect"))
    )
    (net (code "88") (name "unconnected-(U6-NC_2-Pad6)") (class "Default")
      (node (ref "U6") (pin "6") (pinfunction "NC_2_6") (pintype "no_connect"))
    )
    (net (code "89") (name "unconnected-(U6-NC_3-Pad12)") (class "Default")
      (node (ref "U6") (pin "12") (pinfunction "NC_3_12") (pintype "no_connect"))
    )
    (net (code "90") (name "unconnected-(U6-NC_4-Pad15)") (class "Default")
      (node (ref "U6") (pin "15") (pinfunction "NC_4_15") (pintype "no_connect"))
    )
    (net (code "91") (name "unconnected-(U6-NC_5-Pad19)") (class "Default")
      (node (ref "U6") (pin "19") (pinfunction "NC_5_19") (pintype "no_connect"))
    )
    (net (code "92") (name "unconnected-(U6-NC_6-Pad21)") (class "Default")
      (node (ref "U6") (pin "21") (pinfunction "NC_6_21") (pintype "no_connect"))
    )
    (net (code "93") (name "unconnected-(U6-NINT0{slash}GPIO0{slash}XSTBY-Pad9)") (class "Default")
      (node (ref "U6") (pin "9") (pinfunction "NINT0/GPIO0/XSTBY_9") (pintype "bidirectional"))
    )
    (net (code "94") (name "unconnected-(U6-NINT1{slash}GPIO1-Pad8)") (class "Default")
      (node (ref "U6") (pin "8") (pinfunction "NINT1/GPIO1_8") (pintype "bidirectional"))
    )
    (net (code "95") (name "unconnected-(U7-CLKO{slash}SOF-Pad2)") (class "Default")
      (node (ref "U7") (pin "2") (pinfunction "CLKO/SOF_2") (pintype "output"))
    )
    (net (code "96") (name "unconnected-(U7-NC-Pad27)") (class "Default")
      (node (ref "U7") (pin "27") (pinfunction "NC_27") (pintype "no_connect"))
    )
    (net (code "97") (name "unconnected-(U7-NC_2-Pad6)") (class "Default")
      (node (ref "U7") (pin "6") (pinfunction "NC_2_6") (pintype "no_connect"))
    )
    (net (code "98") (name "unconnected-(U7-NC_3-Pad12)") (class "Default")
      (node (ref "U7") (pin "12") (pinfunction "NC_3_12") (pintype "no_connect"))
    )
    (net (code "99") (name "unconnected-(U7-NC_4-Pad15)") (class "Default")
      (node (ref "U7") (pin "15") (pinfunction "NC_4_15") (pintype "no_connect"))
    )
    (net (code "100") (name "unconnected-(U7-NC_5-Pad19)") (class "Default")
      (node (ref "U7") (pin "19") (pinfunction "NC_5_19") (pintype "no_connect"))
    )
    (net (code "101") (name "unconnected-(U7-NC_6-Pad21)") (class "Default")
      (node (ref "U7") (pin "21") (pinfunction "NC_6_21") (pintype "no_connect"))
    )
    (net (code "102") (name "unconnected-(U7-NINT0{slash}GPIO0{slash}XSTBY-Pad9)") (class "Default")
      (node (ref "U7") (pin "9") (pinfunction "NINT0/GPIO0/XSTBY_9") (pintype "bidirectional"))
    )
    (net (code "103") (name "unconnected-(U7-NINT1{slash}GPIO1-Pad8)") (class "Default")
      (node (ref "U7") (pin "8") (pinfunction "NINT1/GPIO1_8") (pintype "bidirectional"))
    )
  )
)
